# ATTAMI-Shield-charge.net
KiCad netlist of a schematic drawn in EAGLE
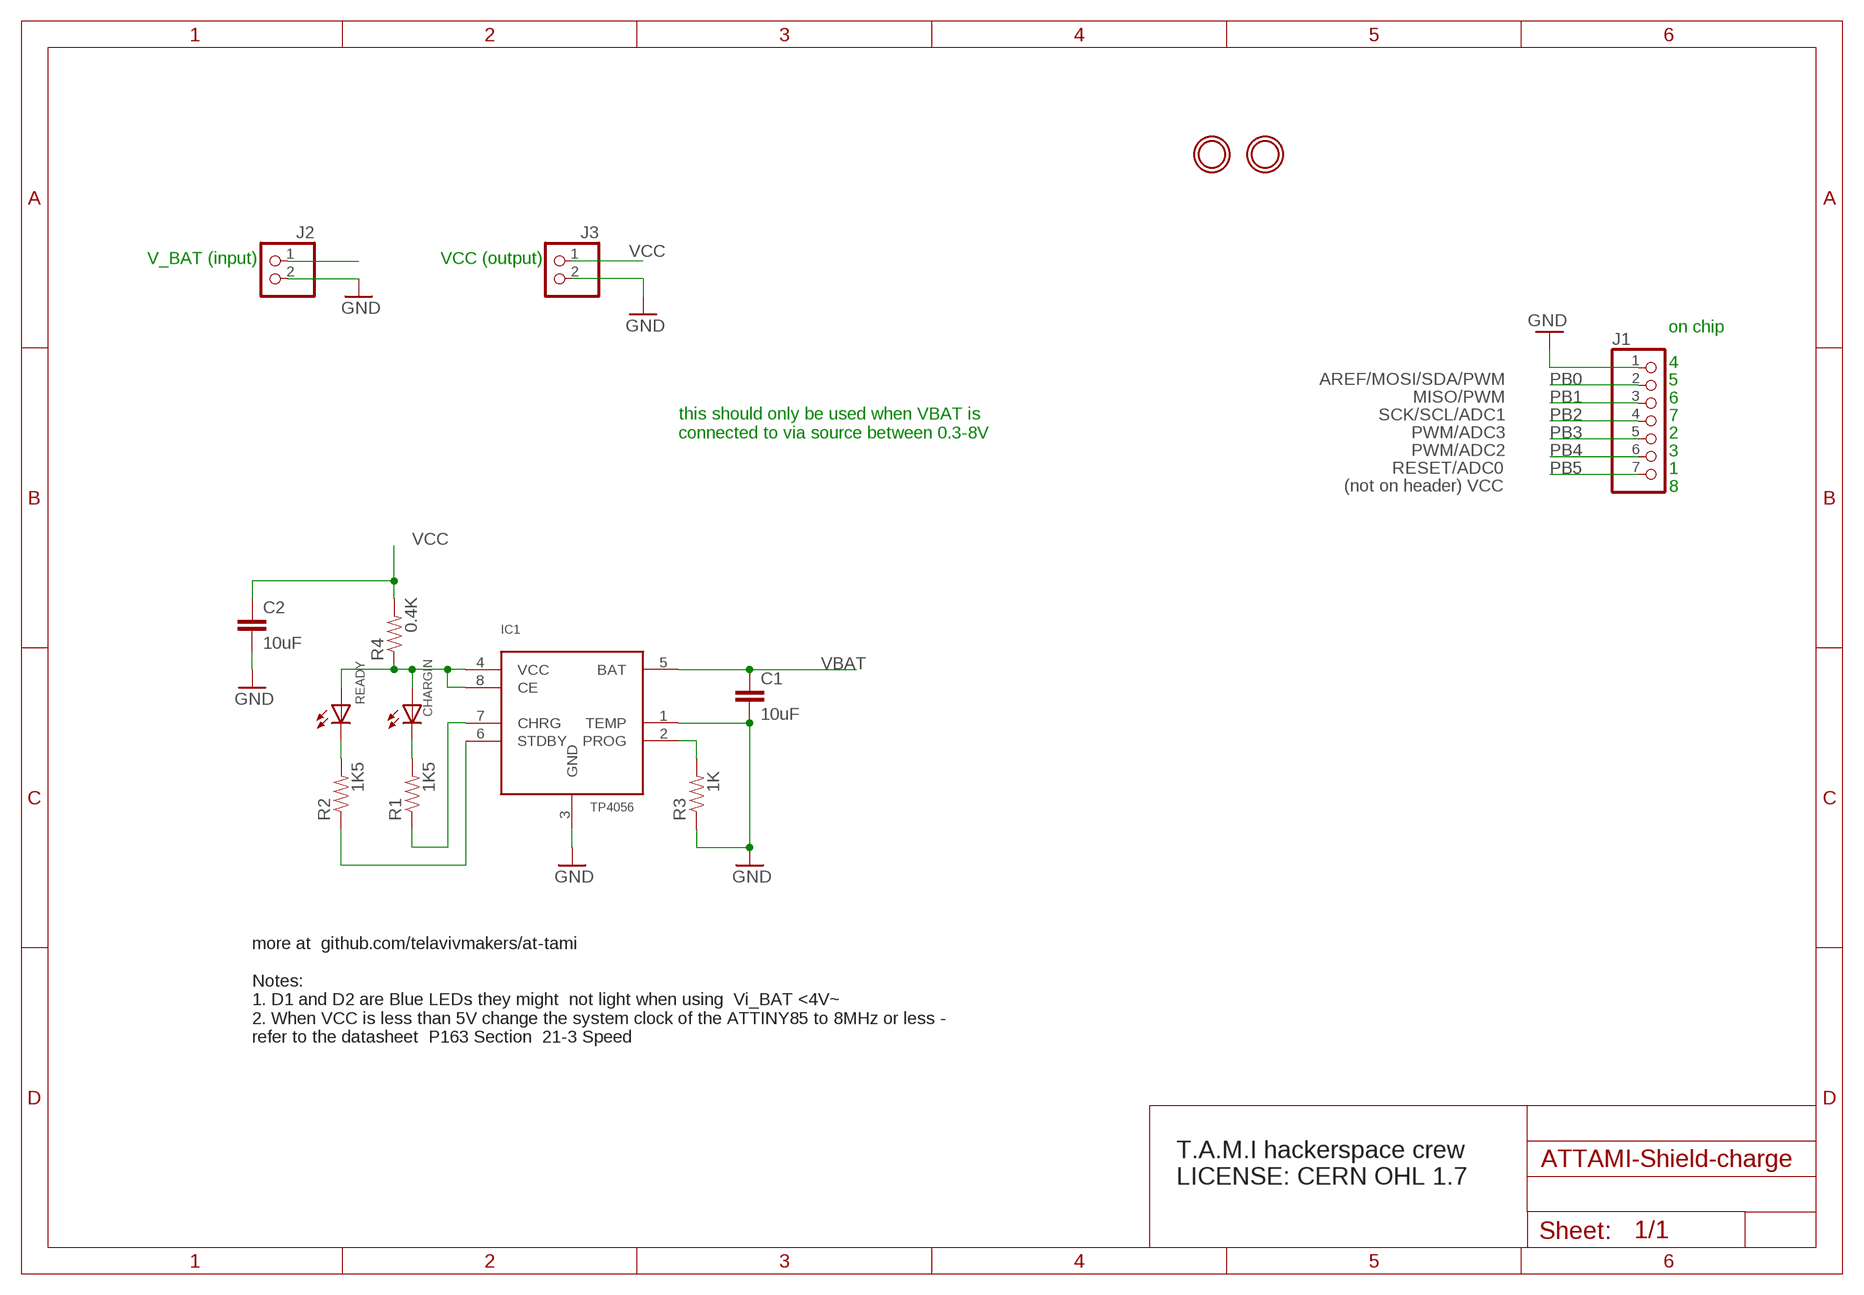
[diagram p0: schematic, sheet 1]

(export (version "E")
  (design (tool "Eeschema 10.0.6"))
  (components
    (comp (ref "C1")
      (value "10uF")
      (footprint "eagle-import:0805")
      (libsource (lib "eagle-import") (part "CAP0805"))
    )
    (comp (ref "C2")
      (value "10uF")
      (footprint "eagle-import:0805")
      (libsource (lib "eagle-import") (part "CAP0805"))
    )
    (comp (ref "CHARGIN")
      (value "LED-0805")
      (footprint "eagle-import:LED-805")
      (libsource (lib "eagle-import") (part "LED-0805"))
    )
    (comp (ref "IC1")
      (value "TP4056")
      (footprint "eagle-import:SOP-8")
      (libsource (lib "eagle-import") (part "TP4056"))
    )
    (comp (ref "J1")
      (value "HEADER-1X7ROUND")
      (footprint "eagle-import:1X07_ROUND")
      (libsource (lib "eagle-import") (part "HEADER-1X7ROUND"))
    )
    (comp (ref "J2")
      (value "HEADER-1X2ROUND")
      (footprint "eagle-import:1X02_ROUND")
      (libsource (lib "eagle-import") (part "HEADER-1X2ROUND"))
    )
    (comp (ref "J3")
      (value "HEADER-1X2ROUND")
      (footprint "eagle-import:1X02_ROUND")
      (libsource (lib "eagle-import") (part "HEADER-1X2ROUND"))
    )
    (comp (ref "R1")
      (value "1K5")
      (footprint "eagle-import:0805")
      (libsource (lib "eagle-import") (part "RESISTOR0805-RES"))
    )
    (comp (ref "R2")
      (value "1K5")
      (footprint "eagle-import:0805")
      (libsource (lib "eagle-import") (part "RESISTOR0805-RES"))
    )
    (comp (ref "R3")
      (value "1K")
      (footprint "eagle-import:0805")
      (libsource (lib "eagle-import") (part "RESISTOR0805-RES"))
    )
    (comp (ref "R4")
      (value "0.4K")
      (footprint "eagle-import:0805")
      (libsource (lib "eagle-import") (part "RESISTOR0805-RES"))
    )
    (comp (ref "READY")
      (value "LED-0805")
      (footprint "eagle-import:LED-805")
      (libsource (lib "eagle-import") (part "LED-0805"))
    )
    (comp (ref "U$1")
      (value "MOUNTINGHOLE2.0")
      (footprint "eagle-import:MOUNTINGHOLE_2.0_PLATED")
      (libsource (lib "eagle-import") (part "MOUNTINGHOLE2.0"))
    )
    (comp (ref "U$2")
      (value "MOUNTINGHOLE2.0")
      (footprint "eagle-import:MOUNTINGHOLE_2.0_PLATED")
      (libsource (lib "eagle-import") (part "MOUNTINGHOLE2.0"))
    )
  )
  (nets
    (net (code "1") (name "/PB0") (class "Default")
      (node (ref "J1") (pin "2") (pinfunction "2_2") (pintype "passive"))
    )
    (net (code "2") (name "/PB1") (class "Default")
      (node (ref "J1") (pin "3") (pinfunction "3_3") (pintype "passive"))
    )
    (net (code "3") (name "/PB2") (class "Default")
      (node (ref "J1") (pin "4") (pinfunction "4_4") (pintype "passive"))
    )
    (net (code "4") (name "/PB3") (class "Default")
      (node (ref "J1") (pin "5") (pinfunction "5_5") (pintype "passive"))
    )
    (net (code "5") (name "/PB4") (class "Default")
      (node (ref "J1") (pin "6") (pinfunction "6_6") (pintype "passive"))
    )
    (net (code "6") (name "/PB5") (class "Default")
      (node (ref "J1") (pin "7") (pinfunction "7_7") (pintype "passive"))
    )
    (net (code "7") (name "/VBAT") (class "Default")
      (node (ref "C1") (pin "1") (pinfunction "1_1") (pintype "passive"))
      (node (ref "IC1") (pin "5") (pinfunction "BAT_5") (pintype "bidirectional"))
      (node (ref "J2") (pin "1") (pinfunction "1_1") (pintype "passive"))
    )
    (net (code "8") (name "/VCC") (class "Default")
      (node (ref "C2") (pin "1") (pinfunction "1_1") (pintype "passive"))
      (node (ref "J3") (pin "1") (pinfunction "1_1") (pintype "passive"))
      (node (ref "R4") (pin "2") (pinfunction "2_2") (pintype "passive"))
    )
    (net (code "9") (name "GND") (class "Default")
      (node (ref "C1") (pin "2") (pinfunction "2_2") (pintype "passive"))
      (node (ref "C2") (pin "2") (pinfunction "2_2") (pintype "passive"))
      (node (ref "IC1") (pin "1") (pinfunction "TEMP_1") (pintype "bidirectional"))
      (node (ref "IC1") (pin "3") (pinfunction "GND_3") (pintype "bidirectional"))
      (node (ref "J1") (pin "1") (pinfunction "1_1") (pintype "passive"))
      (node (ref "J2") (pin "2") (pinfunction "2_2") (pintype "passive"))
      (node (ref "J3") (pin "2") (pinfunction "2_2") (pintype "passive"))
      (node (ref "R3") (pin "1") (pinfunction "1_1") (pintype "passive"))
    )
    (net (code "10") (name "Net-(CHARGIN-PadC)") (class "Default")
      (node (ref "CHARGIN") (pin "C") (pinfunction "C_C") (pintype "passive"))
      (node (ref "R1") (pin "2") (pinfunction "2_2") (pintype "passive"))
    )
    (net (code "11") (name "Net-(IC1-CE)") (class "Default")
      (node (ref "CHARGIN") (pin "A") (pinfunction "A_A") (pintype "passive"))
      (node (ref "IC1") (pin "4") (pinfunction "VCC_4") (pintype "bidirectional"))
      (node (ref "IC1") (pin "8") (pinfunction "CE_8") (pintype "bidirectional"))
      (node (ref "R4") (pin "1") (pinfunction "1_1") (pintype "passive"))
      (node (ref "READY") (pin "A") (pinfunction "A_A") (pintype "passive"))
    )
    (net (code "12") (name "Net-(IC1-CHRG)") (class "Default")
      (node (ref "IC1") (pin "7") (pinfunction "CHRG_7") (pintype "bidirectional"))
      (node (ref "R1") (pin "1") (pinfunction "1_1") (pintype "passive"))
    )
    (net (code "13") (name "Net-(IC1-PROG)") (class "Default")
      (node (ref "IC1") (pin "2") (pinfunction "PROG_2") (pintype "bidirectional"))
      (node (ref "R3") (pin "2") (pinfunction "2_2") (pintype "passive"))
    )
    (net (code "14") (name "Net-(IC1-STDBY)") (class "Default")
      (node (ref "IC1") (pin "6") (pinfunction "STDBY_6") (pintype "bidirectional"))
      (node (ref "R2") (pin "1") (pinfunction "1_1") (pintype "passive"))
    )
    (net (code "15") (name "Net-(R2-Pad2)") (class "Default")
      (node (ref "R2") (pin "2") (pinfunction "2_2") (pintype "passive"))
      (node (ref "READY") (pin "C") (pinfunction "C_C") (pintype "passive"))
    )
  )
)
